# Boost-converter-controller.net
KiCad netlist of a schematic drawn in Altium Designer
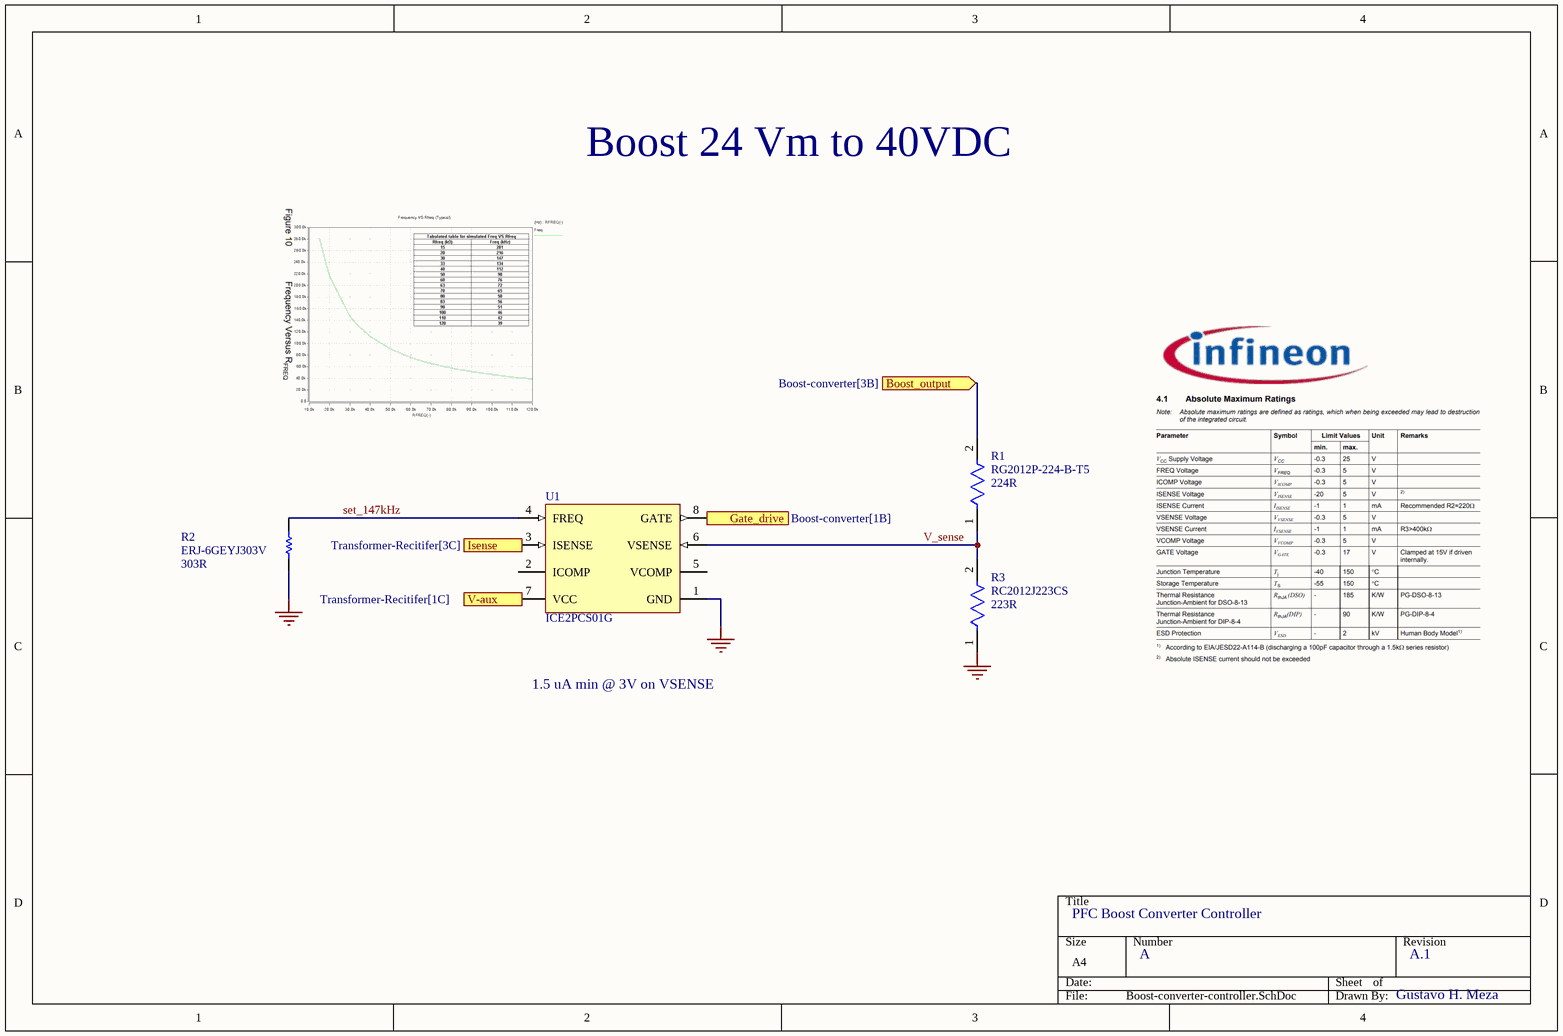
[diagram p0: Boost-converter-controller.SchDoc]

(export (version "E")
  (design (tool "Eeschema 10.0.6"))
  (components
    (comp (ref "R1")
      (value "RG2012P-224-B-T5")
      (footprint "FP-RG2012-IPC_A")
      (description "Automotive Metal Thin Film Chip Resistor, 0805, 220kΩ, 0.1%, 25ppm/°C, 0.125W, 150V")
      (fields (field (name "RESISTANCE") "224R") (field (name "TOLERANCE") "0.1%"))
      (libsource (lib "Altium Content Vault") (part "1029c3af85768c4190bb7ad29bc67b5"))
    )
    (comp (ref "R2")
      (value "ERJ-6GEYJ303V")
      (footprint "RESC2013X70X40NL20T20")
      (fields (field (name "MANUFACTURER") "Panasonic") (field (name "RESISTANCE") "303R"))
      (libsource (lib "Altium Content Vault") (part "RES"))
    )
    (comp (ref "R3")
      (value "RC2012J223CS")
      (footprint "FP-RC2012-IPC_A")
      (description "Res Thick Film 0805 22kΩ 5% 0.125W ±100ppm/°C Molded SMD T/R")
      (fields (field (name "TOLERANCE") "5%") (field (name "RESISTANCE") "223R"))
      (libsource (lib "Altium Content Vault") (part "1029c3af85768c4190bb7ad29bc67b5"))
    )
    (comp (ref "U1")
      (value "ICE2PCS01G")
      (footprint "INF-PG-DSO-8-16_N")
      (fields (field (name "MANUFACTURER") "Infineon"))
      (libsource (lib "Altium Content Vault") (part "INF-ICE2PCS0X-PG-DIP_SDO-8"))
    )
  )
  (nets
    (net (code "1") (name "/Boost_output") (class "Default")
      (node (ref "R1") (pin "2") (pinfunction "2_2") (pintype "passive"))
    )
    (net (code "2") (name "/Gate_drive") (class "Default")
      (node (ref "U1") (pin "8") (pinfunction "GATE_8") (pintype "output"))
    )
    (net (code "5") (name "/V_sense") (class "Default")
      (node (ref "R1") (pin "1") (pinfunction "1_1") (pintype "passive"))
      (node (ref "R3") (pin "2") (pinfunction "2_2") (pintype "passive"))
      (node (ref "U1") (pin "6") (pinfunction "VSENSE_6") (pintype "input"))
    )
    (net (code "6") (name "/set_147kHz") (class "Default")
      (node (ref "R2") (pin "2") (pinfunction "2_2") (pintype "passive"))
      (node (ref "U1") (pin "4") (pinfunction "FREQ_4") (pintype "input"))
    )
    (net (code "7") (name "GND") (class "Default")
      (node (ref "R2") (pin "1") (pinfunction "1_1") (pintype "passive"))
      (node (ref "R3") (pin "1") (pinfunction "1_1") (pintype "passive"))
      (node (ref "U1") (pin "1") (pinfunction "GND_1") (pintype "power_in"))
    )
    (net (code "8") (name "unconnected-(U1-ICOMP-Pad2)") (class "Default")
      (node (ref "U1") (pin "2") (pinfunction "ICOMP_2") (pintype "passive"))
    )
    (net (code "9") (name "unconnected-(U1-ISENSE-Pad3)") (class "Default")
      (node (ref "U1") (pin "3") (pinfunction "ISENSE_3") (pintype "input"))
    )
    (net (code "10") (name "unconnected-(U1-VCC-Pad7)") (class "Default")
      (node (ref "U1") (pin "7") (pinfunction "VCC_7") (pintype "power_in"))
    )
    (net (code "11") (name "unconnected-(U1-VCOMP-Pad5)") (class "Default")
      (node (ref "U1") (pin "5") (pinfunction "VCOMP_5") (pintype "passive"))
    )
  )
)
